# 1-Schematic_BluePill.net
KiCad netlist of a schematic drawn in EasyEDA
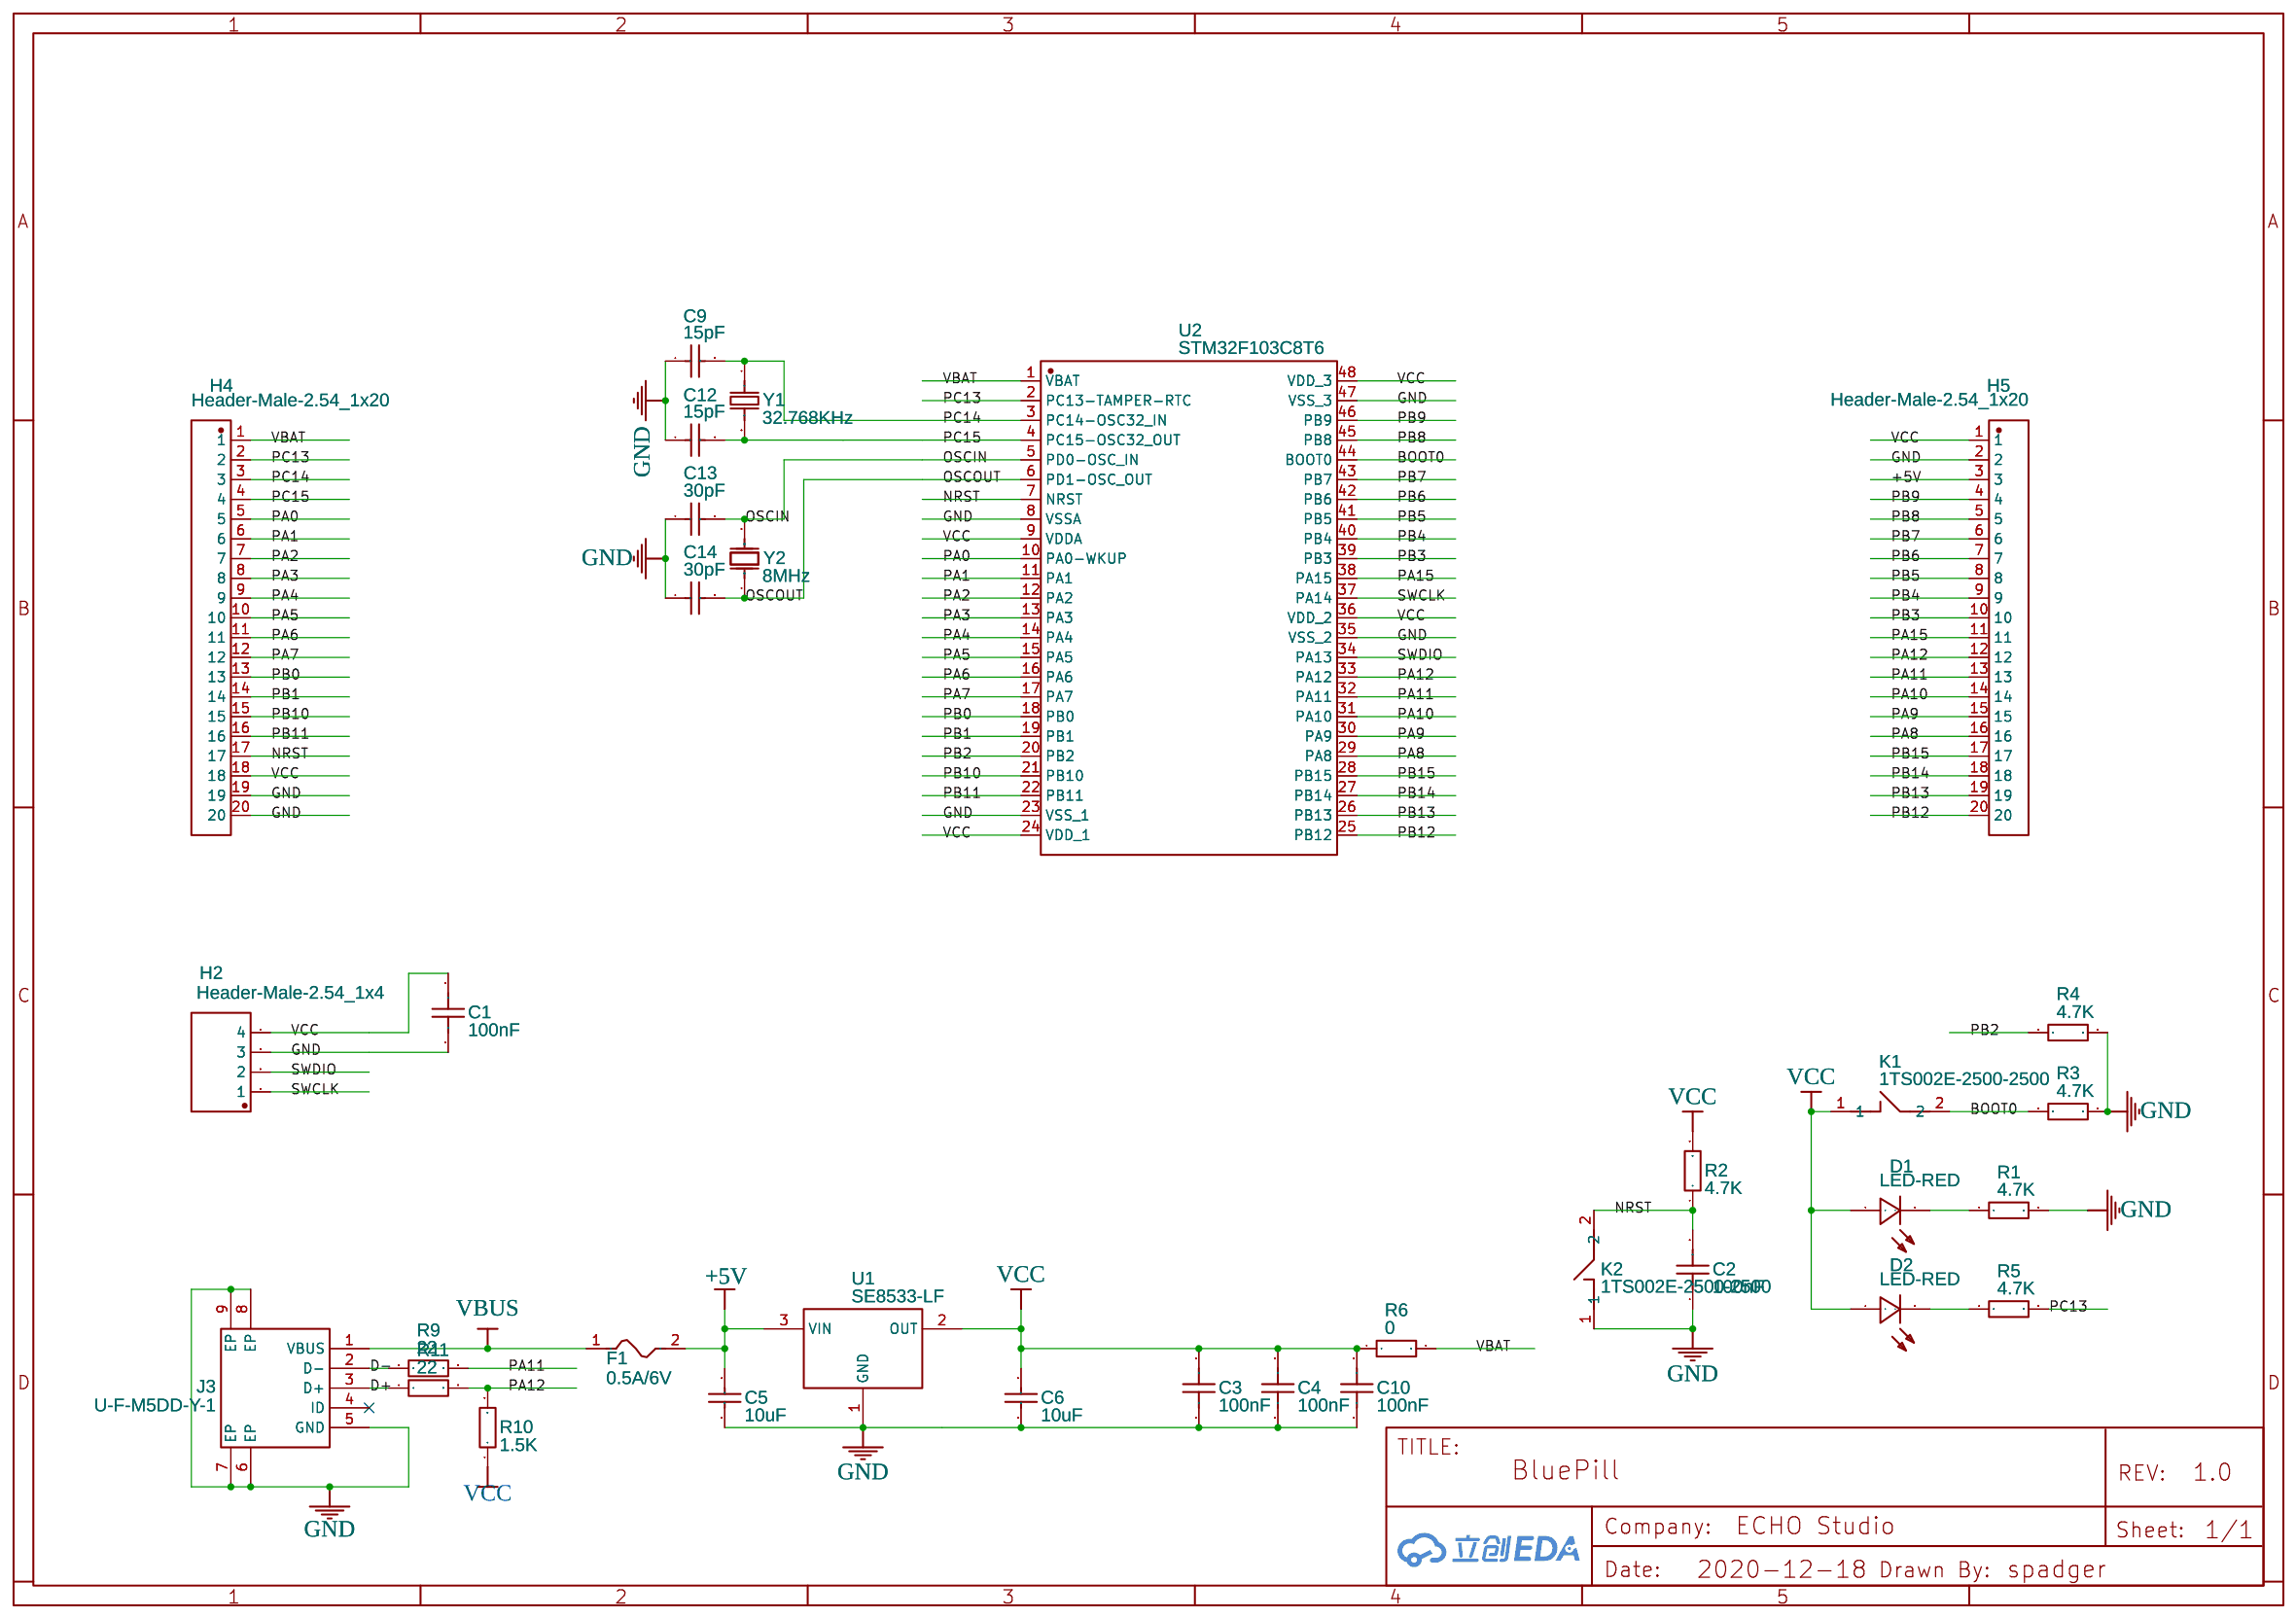
[diagram p0: schematic sheet]

(export (version "E")
  (design (tool "Eeschema 10.0.6"))
  (components
    (comp (ref "C1")
      (value "100nF")
      (fields
        (field (name "BOM_Manufacturer Part") "CC0603KRX7R9BB104")
        (field (name "BOM_Supplier Part") "C14663")
      )
      (libsource (lib "") (part "CC0603KRX7R9BB104"))
    )
    (comp (ref "C2")
      (value "100nF")
      (fields
        (field (name "BOM_Manufacturer Part") "CC0603KRX7R9BB104")
        (field (name "BOM_Supplier Part") "C14663")
      )
      (libsource (lib "") (part "CC0603KRX7R9BB104"))
    )
    (comp (ref "C3")
      (value "100nF")
      (fields
        (field (name "BOM_Manufacturer Part") "CC0603KRX7R9BB104")
        (field (name "BOM_Supplier Part") "C14663")
      )
      (libsource (lib "") (part "CC0603KRX7R9BB104"))
    )
    (comp (ref "C4")
      (value "100nF")
      (fields
        (field (name "BOM_Manufacturer Part") "CC0603KRX7R9BB104")
        (field (name "BOM_Supplier Part") "C14663")
      )
      (libsource (lib "") (part "CC0603KRX7R9BB104"))
    )
    (comp (ref "C5")
      (value "10uF")
      (fields
        (field (name "BOM_Manufacturer Part") "CL21A106KAYNNNE")
        (field (name "BOM_Supplier Part") "C15850")
      )
      (libsource (lib "") (part "CL21A106KAYNNNE"))
    )
    (comp (ref "C6")
      (value "10uF")
      (fields
        (field (name "BOM_Manufacturer Part") "CL21A106KAYNNNE")
        (field (name "BOM_Supplier Part") "C15850")
      )
      (libsource (lib "") (part "CL21A106KAYNNNE"))
    )
    (comp (ref "C9")
      (value "15pF")
      (fields
        (field (name "BOM_Manufacturer Part") "CL10C150JB8NNNC")
        (field (name "BOM_Supplier Part") "C1644")
      )
      (libsource (lib "") (part "CL10C150JB8NNNC"))
    )
    (comp (ref "C10")
      (value "100nF")
      (fields
        (field (name "BOM_Manufacturer Part") "CC0603KRX7R9BB104")
        (field (name "BOM_Supplier Part") "C14663")
      )
      (libsource (lib "") (part "CC0603KRX7R9BB104"))
    )
    (comp (ref "C12")
      (value "15pF")
      (fields
        (field (name "BOM_Manufacturer Part") "CL10C150JB8NNNC")
        (field (name "BOM_Supplier Part") "C1644")
      )
      (libsource (lib "") (part "CL10C150JB8NNNC"))
    )
    (comp (ref "C13")
      (value "30pF")
      (fields
        (field (name "BOM_Manufacturer Part") "CL10C300JB8NNNC")
        (field (name "BOM_Supplier Part") "C22397")
      )
      (libsource (lib "") (part "CL10C300JB8NNNC"))
    )
    (comp (ref "C14")
      (value "30pF")
      (fields
        (field (name "BOM_Manufacturer Part") "CL10C300JB8NNNC")
        (field (name "BOM_Supplier Part") "C22397")
      )
      (libsource (lib "") (part "CL10C300JB8NNNC"))
    )
    (comp (ref "D1")
      (value "LED-RED")
      (fields
        (field (name "BOM_Manufacturer Part") "FC-DA1608UGK-520D10")
        (field (name "BOM_Supplier Part") "C84267")
      )
      (libsource (lib "") (part "Unknown_950_-195"))
    )
    (comp (ref "D2")
      (value "LED-RED")
      (fields
        (field (name "BOM_Manufacturer Part") "FC-DA1608UGK-520D10")
        (field (name "BOM_Supplier Part") "C84267")
      )
      (libsource (lib "") (part "Unknown_950_-145"))
    )
    (comp (ref "F1")
      (value "0.5A/6V")
      (fields
        (field (name "BOM_Manufacturer Part") "SMD0805P050TF")
        (field (name "BOM_Supplier Part") "C130286")
      )
      (libsource (lib "") (part "Unknown_315_-135"))
    )
    (comp (ref "H2")
      (value "Header-Male-2.54_1x4")
      (fields
        (field (name "BOM_Manufacturer Part") "210S-1*4P L=11.6MMGold-plated black")
        (field (name "BOM_Supplier Part") "C124378")
      )
      (libsource (lib "") (part "Header-Male-2.54_1x4"))
    )
    (comp (ref "H4")
      (value "Header-Male-2.54_1x20")
      (fields
        (field (name "BOM_Manufacturer Part") "2.54mm 1*20PHeader")
        (field (name "BOM_Supplier Part") "C50981")
      )
      (libsource (lib "") (part "Header-Male-2.54_1x20"))
    )
    (comp (ref "H5")
      (value "Header-Male-2.54_1x20")
      (fields
        (field (name "BOM_Manufacturer Part") "2.54mm 1*20PHeader")
        (field (name "BOM_Supplier Part") "C50981")
      )
      (libsource (lib "") (part "Header-Male-2.54_1x20_1"))
    )
    (comp (ref "J3")
      (value "U-F-M5DD-Y-1")
      (fields (field (name "BOM_Supplier Part") "C91467"))
      (libsource (lib "") (part "U-F-M5DD-Y-1"))
    )
    (comp (ref "K1")
      (value "1TS002E-2500-2500")
      (fields (field (name "BOM_Supplier Part") "C329185"))
      (libsource (lib "") (part "1TS002E-2500-2500_1"))
    )
    (comp (ref "K2")
      (value "1TS002E-2500-2500")
      (fields (field (name "BOM_Supplier Part") "C329185"))
      (libsource (lib "") (part "1TS002E-2500-2500"))
    )
    (comp (ref "R1")
      (value "4.7K")
      (fields
        (field (name "BOM_Manufacturer Part") "0603WAF4701T5E")
        (field (name "BOM_Supplier Part") "C23162")
      )
      (libsource (lib "") (part "0603WAF4701T5E_1"))
    )
    (comp (ref "R2")
      (value "4.7K")
      (fields
        (field (name "BOM_Manufacturer Part") "0603WAF4701T5E")
        (field (name "BOM_Supplier Part") "C23162")
      )
      (libsource (lib "") (part "0603WAF4701T5E_2"))
    )
    (comp (ref "R3")
      (value "4.7K")
      (fields
        (field (name "BOM_Manufacturer Part") "0603WAF4701T5E")
        (field (name "BOM_Supplier Part") "C23162")
      )
      (libsource (lib "") (part "0603WAF4701T5E"))
    )
    (comp (ref "R4")
      (value "4.7K")
      (fields
        (field (name "BOM_Manufacturer Part") "0603WAF4701T5E")
        (field (name "BOM_Supplier Part") "C23162")
      )
      (libsource (lib "") (part "0603WAF4701T5E_1"))
    )
    (comp (ref "R5")
      (value "4.7K")
      (fields
        (field (name "BOM_Manufacturer Part") "0603WAF4701T5E")
        (field (name "BOM_Supplier Part") "C23162")
      )
      (libsource (lib "") (part "0603WAF4701T5E_1"))
    )
    (comp (ref "R6")
      (value "0")
      (fields
        (field (name "BOM_Manufacturer Part") "0603WAF0000T5E")
        (field (name "BOM_Supplier Part") "C21189")
      )
      (libsource (lib "") (part "0603WAF0000T5E"))
    )
    (comp (ref "R9")
      (value "22")
      (fields
        (field (name "BOM_Manufacturer Part") "0603WAF220JT5E")
        (field (name "BOM_Supplier Part") "C23345")
      )
      (libsource (lib "") (part "0603WAF220JT5E"))
    )
    (comp (ref "R10")
      (value "1.5K")
      (fields
        (field (name "BOM_Manufacturer Part") "0603WAF1501T5E")
        (field (name "BOM_Supplier Part") "C22843")
      )
      (libsource (lib "") (part "0603WAF1501T5E"))
    )
    (comp (ref "R11")
      (value "22")
      (fields
        (field (name "BOM_Manufacturer Part") "0603WAF220JT5E")
        (field (name "BOM_Supplier Part") "C23345")
      )
      (libsource (lib "") (part "0603WAF220JT5E"))
    )
    (comp (ref "U1")
      (value "SE8533-LF")
      (fields (field (name "BOM_Supplier Part") "C115016"))
      (libsource (lib "") (part "SE8533-LF"))
    )
    (comp (ref "U2")
      (value "STM32F103C8T6")
      (fields (field (name "BOM_Supplier Part") "C8734"))
      (libsource (lib "") (part "STM32F103C8T6"))
    )
    (comp (ref "Y1")
      (value "32.768KHz")
      (fields
        (field (name "BOM_Manufacturer Part") "DT-38 32.768KHz")
        (field (name "BOM_Supplier Part") "C93228")
      )
      (libsource (lib "") (part "DT-38 32.768KHz"))
    )
    (comp (ref "Y2")
      (value "8MHz")
      (fields (field (name "BOM_Supplier Part") "C107425"))
      (libsource (lib "") (part "HC-49S 8MHz 20pF 30PPM"))
    )
  )
  (nets
    (net (code "1") (name "+5V") (class "Default")
      (node (ref "C5") (pin "2") (pinfunction "2_2") (pintype "input"))
      (node (ref "F1") (pin "2") (pinfunction "2_2") (pintype "unspecified"))
      (node (ref "H5") (pin "3") (pinfunction "3_3") (pintype "unspecified"))
      (node (ref "U1") (pin "3") (pinfunction "VIN_3") (pintype "unspecified"))
    )
    (net (code "2") (name "/BOOT0") (class "Default")
      (node (ref "K1") (pin "2") (pinfunction "2_2") (pintype "unspecified"))
      (node (ref "R3") (pin "2") (pinfunction "2_2") (pintype "input"))
      (node (ref "U2") (pin "44") (pinfunction "BOOT0_44") (pintype "unspecified"))
    )
    (net (code "3") (name "/D+") (class "Default")
      (node (ref "J3") (pin "3") (pinfunction "D+_3") (pintype "unspecified"))
      (node (ref "R11") (pin "1") (pinfunction "1_1") (pintype "input"))
    )
    (net (code "4") (name "/D-") (class "Default")
      (node (ref "J3") (pin "2") (pinfunction "D-_2") (pintype "unspecified"))
      (node (ref "R9") (pin "1") (pinfunction "1_1") (pintype "input"))
    )
    (net (code "5") (name "/NRST") (class "Default")
      (node (ref "C2") (pin "2") (pinfunction "2_2") (pintype "unspecified"))
      (node (ref "H4") (pin "17") (pinfunction "17_17") (pintype "unspecified"))
      (node (ref "K2") (pin "2") (pinfunction "2_2") (pintype "unspecified"))
      (node (ref "R2") (pin "1") (pinfunction "1_1") (pintype "input"))
      (node (ref "U2") (pin "7") (pinfunction "NRST_7") (pintype "unspecified"))
    )
    (net (code "6") (name "/OSCIN") (class "Default")
      (node (ref "C13") (pin "2") (pinfunction "2_2") (pintype "input"))
      (node (ref "U2") (pin "5") (pinfunction "PD0-OSC_IN_5") (pintype "unspecified"))
      (node (ref "Y2") (pin "2") (pinfunction "OSC2_2") (pintype "input"))
    )
    (net (code "7") (name "/OSCOUT") (class "Default")
      (node (ref "C14") (pin "2") (pinfunction "2_2") (pintype "input"))
      (node (ref "U2") (pin "6") (pinfunction "PD1-OSC_OUT_6") (pintype "unspecified"))
      (node (ref "Y2") (pin "1") (pinfunction "OSC1_1") (pintype "input"))
    )
    (net (code "8") (name "/PA0") (class "Default")
      (node (ref "H4") (pin "5") (pinfunction "5_5") (pintype "unspecified"))
      (node (ref "U2") (pin "10") (pinfunction "PA0-WKUP_10") (pintype "unspecified"))
    )
    (net (code "9") (name "/PA1") (class "Default")
      (node (ref "H4") (pin "6") (pinfunction "6_6") (pintype "unspecified"))
      (node (ref "U2") (pin "11") (pinfunction "PA1_11") (pintype "unspecified"))
    )
    (net (code "10") (name "/PA2") (class "Default")
      (node (ref "H4") (pin "7") (pinfunction "7_7") (pintype "unspecified"))
      (node (ref "U2") (pin "12") (pinfunction "PA2_12") (pintype "unspecified"))
    )
    (net (code "11") (name "/PA3") (class "Default")
      (node (ref "H4") (pin "8") (pinfunction "8_8") (pintype "unspecified"))
      (node (ref "U2") (pin "13") (pinfunction "PA3_13") (pintype "unspecified"))
    )
    (net (code "12") (name "/PA4") (class "Default")
      (node (ref "H4") (pin "9") (pinfunction "9_9") (pintype "unspecified"))
      (node (ref "U2") (pin "14") (pinfunction "PA4_14") (pintype "unspecified"))
    )
    (net (code "13") (name "/PA5") (class "Default")
      (node (ref "H4") (pin "10") (pinfunction "10_10") (pintype "unspecified"))
      (node (ref "U2") (pin "15") (pinfunction "PA5_15") (pintype "unspecified"))
    )
    (net (code "14") (name "/PA6") (class "Default")
      (node (ref "H4") (pin "11") (pinfunction "11_11") (pintype "unspecified"))
      (node (ref "U2") (pin "16") (pinfunction "PA6_16") (pintype "unspecified"))
    )
    (net (code "15") (name "/PA7") (class "Default")
      (node (ref "H4") (pin "12") (pinfunction "12_12") (pintype "unspecified"))
      (node (ref "U2") (pin "17") (pinfunction "PA7_17") (pintype "unspecified"))
    )
    (net (code "16") (name "/PA8") (class "Default")
      (node (ref "H5") (pin "16") (pinfunction "16_16") (pintype "unspecified"))
      (node (ref "U2") (pin "29") (pinfunction "PA8_29") (pintype "unspecified"))
    )
    (net (code "17") (name "/PA9") (class "Default")
      (node (ref "H5") (pin "15") (pinfunction "15_15") (pintype "unspecified"))
      (node (ref "U2") (pin "30") (pinfunction "PA9_30") (pintype "unspecified"))
    )
    (net (code "18") (name "/PA10") (class "Default")
      (node (ref "H5") (pin "14") (pinfunction "14_14") (pintype "unspecified"))
      (node (ref "U2") (pin "31") (pinfunction "PA10_31") (pintype "unspecified"))
    )
    (net (code "19") (name "/PA11") (class "Default")
      (node (ref "H5") (pin "13") (pinfunction "13_13") (pintype "unspecified"))
      (node (ref "R9") (pin "2") (pinfunction "2_2") (pintype "input"))
      (node (ref "U2") (pin "32") (pinfunction "PA11_32") (pintype "unspecified"))
    )
    (net (code "20") (name "/PA12") (class "Default")
      (node (ref "H5") (pin "12") (pinfunction "12_12") (pintype "unspecified"))
      (node (ref "R10") (pin "2") (pinfunction "2_2") (pintype "input"))
      (node (ref "R11") (pin "2") (pinfunction "2_2") (pintype "input"))
      (node (ref "U2") (pin "33") (pinfunction "PA12_33") (pintype "unspecified"))
    )
    (net (code "21") (name "/PA15") (class "Default")
      (node (ref "H5") (pin "11") (pinfunction "11_11") (pintype "unspecified"))
      (node (ref "U2") (pin "38") (pinfunction "PA15_38") (pintype "unspecified"))
    )
    (net (code "22") (name "/PB0") (class "Default")
      (node (ref "H4") (pin "13") (pinfunction "13_13") (pintype "unspecified"))
      (node (ref "U2") (pin "18") (pinfunction "PB0_18") (pintype "unspecified"))
    )
    (net (code "23") (name "/PB1") (class "Default")
      (node (ref "H4") (pin "14") (pinfunction "14_14") (pintype "unspecified"))
      (node (ref "U2") (pin "19") (pinfunction "PB1_19") (pintype "unspecified"))
    )
    (net (code "24") (name "/PB2") (class "Default")
      (node (ref "R4") (pin "1") (pinfunction "1_1") (pintype "input"))
      (node (ref "U2") (pin "20") (pinfunction "PB2_20") (pintype "unspecified"))
    )
    (net (code "25") (name "/PB3") (class "Default")
      (node (ref "H5") (pin "10") (pinfunction "10_10") (pintype "unspecified"))
      (node (ref "U2") (pin "39") (pinfunction "PB3_39") (pintype "unspecified"))
    )
    (net (code "26") (name "/PB4") (class "Default")
      (node (ref "H5") (pin "9") (pinfunction "9_9") (pintype "unspecified"))
      (node (ref "U2") (pin "40") (pinfunction "PB4_40") (pintype "unspecified"))
    )
    (net (code "27") (name "/PB5") (class "Default")
      (node (ref "H5") (pin "8") (pinfunction "8_8") (pintype "unspecified"))
      (node (ref "U2") (pin "41") (pinfunction "PB5_41") (pintype "unspecified"))
    )
    (net (code "28") (name "/PB6") (class "Default")
      (node (ref "H5") (pin "7") (pinfunction "7_7") (pintype "unspecified"))
      (node (ref "U2") (pin "42") (pinfunction "PB6_42") (pintype "unspecified"))
    )
    (net (code "29") (name "/PB7") (class "Default")
      (node (ref "H5") (pin "6") (pinfunction "6_6") (pintype "unspecified"))
      (node (ref "U2") (pin "43") (pinfunction "PB7_43") (pintype "unspecified"))
    )
    (net (code "30") (name "/PB8") (class "Default")
      (node (ref "H5") (pin "5") (pinfunction "5_5") (pintype "unspecified"))
      (node (ref "U2") (pin "45") (pinfunction "PB8_45") (pintype "unspecified"))
    )
    (net (code "31") (name "/PB9") (class "Default")
      (node (ref "H5") (pin "4") (pinfunction "4_4") (pintype "unspecified"))
      (node (ref "U2") (pin "46") (pinfunction "PB9_46") (pintype "unspecified"))
    )
    (net (code "32") (name "/PB10") (class "Default")
      (node (ref "H4") (pin "15") (pinfunction "15_15") (pintype "unspecified"))
      (node (ref "U2") (pin "21") (pinfunction "PB10_21") (pintype "unspecified"))
    )
    (net (code "33") (name "/PB11") (class "Default")
      (node (ref "H4") (pin "16") (pinfunction "16_16") (pintype "unspecified"))
      (node (ref "U2") (pin "22") (pinfunction "PB11_22") (pintype "unspecified"))
    )
    (net (code "34") (name "/PB12") (class "Default")
      (node (ref "H5") (pin "20") (pinfunction "20_20") (pintype "unspecified"))
      (node (ref "U2") (pin "25") (pinfunction "PB12_25") (pintype "unspecified"))
    )
    (net (code "35") (name "/PB13") (class "Default")
      (node (ref "H5") (pin "19") (pinfunction "19_19") (pintype "unspecified"))
      (node (ref "U2") (pin "26") (pinfunction "PB13_26") (pintype "unspecified"))
    )
    (net (code "36") (name "/PB14") (class "Default")
      (node (ref "H5") (pin "18") (pinfunction "18_18") (pintype "unspecified"))
      (node (ref "U2") (pin "27") (pinfunction "PB14_27") (pintype "unspecified"))
    )
    (net (code "37") (name "/PB15") (class "Default")
      (node (ref "H5") (pin "17") (pinfunction "17_17") (pintype "unspecified"))
      (node (ref "U2") (pin "28") (pinfunction "PB15_28") (pintype "unspecified"))
    )
    (net (code "38") (name "/PC13") (class "Default")
      (node (ref "H4") (pin "2") (pinfunction "2_2") (pintype "unspecified"))
      (node (ref "R5") (pin "2") (pinfunction "2_2") (pintype "input"))
      (node (ref "U2") (pin "2") (pinfunction "PC13-TAMPER-RTC_2") (pintype "unspecified"))
    )
    (net (code "39") (name "/PC14") (class "Default")
      (node (ref "C9") (pin "2") (pinfunction "2_2") (pintype "input"))
      (node (ref "H4") (pin "3") (pinfunction "3_3") (pintype "unspecified"))
      (node (ref "U2") (pin "3") (pinfunction "PC14-OSC32_IN_3") (pintype "unspecified"))
      (node (ref "Y1") (pin "1") (pinfunction "1_1") (pintype "unspecified"))
    )
    (net (code "40") (name "/PC15") (class "Default")
      (node (ref "C12") (pin "2") (pinfunction "2_2") (pintype "input"))
      (node (ref "H4") (pin "4") (pinfunction "4_4") (pintype "unspecified"))
      (node (ref "U2") (pin "4") (pinfunction "PC15-OSC32_OUT_4") (pintype "unspecified"))
      (node (ref "Y1") (pin "2") (pinfunction "2_2") (pintype "unspecified"))
    )
    (net (code "41") (name "/SWCLK") (class "Default")
      (node (ref "H2") (pin "1") (pinfunction "1_1") (pintype "unspecified"))
      (node (ref "U2") (pin "37") (pinfunction "PA14_37") (pintype "unspecified"))
    )
    (net (code "42") (name "/SWDIO") (class "Default")
      (node (ref "H2") (pin "2") (pinfunction "2_2") (pintype "unspecified"))
      (node (ref "U2") (pin "34") (pinfunction "PA13_34") (pintype "unspecified"))
    )
    (net (code "43") (name "/VBAT") (class "Default")
      (node (ref "H4") (pin "1") (pinfunction "1_1") (pintype "unspecified"))
      (node (ref "R6") (pin "2") (pinfunction "2_2") (pintype "input"))
      (node (ref "U2") (pin "1") (pinfunction "VBAT_1") (pintype "unspecified"))
    )
    (net (code "44") (name "GND") (class "Default")
      (node (ref "C1") (pin "1") (pinfunction "1_1") (pintype "unspecified"))
      (node (ref "C10") (pin "1") (pinfunction "1_1") (pintype "unspecified"))
      (node (ref "C12") (pin "1") (pinfunction "1_1") (pintype "input"))
      (node (ref "C13") (pin "1") (pinfunction "1_1") (pintype "input"))
      (node (ref "C14") (pin "1") (pinfunction "1_1") (pintype "input"))
      (node (ref "C2") (pin "1") (pinfunction "1_1") (pintype "unspecified"))
      (node (ref "C3") (pin "1") (pinfunction "1_1") (pintype "unspecified"))
      (node (ref "C4") (pin "1") (pinfunction "1_1") (pintype "unspecified"))
      (node (ref "C5") (pin "1") (pinfunction "1_1") (pintype "input"))
      (node (ref "C6") (pin "1") (pinfunction "1_1") (pintype "input"))
      (node (ref "C9") (pin "1") (pinfunction "1_1") (pintype "input"))
      (node (ref "H2") (pin "3") (pinfunction "3_3") (pintype "unspecified"))
      (node (ref "H4") (pin "19") (pinfunction "19_19") (pintype "unspecified"))
      (node (ref "H4") (pin "20") (pinfunction "20_20") (pintype "unspecified"))
      (node (ref "H5") (pin "2") (pinfunction "2_2") (pintype "unspecified"))
      (node (ref "J3") (pin "5") (pinfunction "GND_5") (pintype "unspecified"))
      (node (ref "J3") (pin "6") (pinfunction "EP_6") (pintype "unspecified"))
      (node (ref "J3") (pin "7") (pinfunction "EP_7") (pintype "unspecified"))
      (node (ref "J3") (pin "8") (pinfunction "EP_8") (pintype "unspecified"))
      (node (ref "J3") (pin "9") (pinfunction "EP_9") (pintype "unspecified"))
      (node (ref "K2") (pin "1") (pinfunction "1_1") (pintype "unspecified"))
      (node (ref "R1") (pin "2") (pinfunction "2_2") (pintype "input"))
      (node (ref "R3") (pin "1") (pinfunction "1_1") (pintype "input"))
      (node (ref "R4") (pin "2") (pinfunction "2_2") (pintype "input"))
      (node (ref "U1") (pin "1") (pinfunction "GND_1") (pintype "unspecified"))
      (node (ref "U2") (pin "23") (pinfunction "VSS_1_23") (pintype "unspecified"))
      (node (ref "U2") (pin "35") (pinfunction "VSS_2_35") (pintype "unspecified"))
      (node (ref "U2") (pin "47") (pinfunction "VSS_3_47") (pintype "unspecified"))
      (node (ref "U2") (pin "8") (pinfunction "VSSA_8") (pintype "unspecified"))
    )
    (net (code "45") (name "Net-(D1--)") (class "Default")
      (node (ref "D1") (pin "2") (pinfunction "-_2") (pintype "unspecified"))
      (node (ref "R1") (pin "1") (pinfunction "1_1") (pintype "input"))
    )
    (net (code "46") (name "Net-(D2--)") (class "Default")
      (node (ref "D2") (pin "2") (pinfunction "-_2") (pintype "unspecified"))
      (node (ref "R5") (pin "1") (pinfunction "1_1") (pintype "input"))
    )
    (net (code "47") (name "VBUS") (class "Default")
      (node (ref "F1") (pin "1") (pinfunction "1_1") (pintype "unspecified"))
      (node (ref "J3") (pin "1") (pinfunction "VBUS_1") (pintype "unspecified"))
    )
    (net (code "48") (name "VCC") (class "Default")
      (node (ref "C1") (pin "2") (pinfunction "2_2") (pintype "unspecified"))
      (node (ref "C10") (pin "2") (pinfunction "2_2") (pintype "unspecified"))
      (node (ref "C3") (pin "2") (pinfunction "2_2") (pintype "unspecified"))
      (node (ref "C4") (pin "2") (pinfunction "2_2") (pintype "unspecified"))
      (node (ref "C6") (pin "2") (pinfunction "2_2") (pintype "input"))
      (node (ref "D1") (pin "1") (pinfunction "+_1") (pintype "unspecified"))
      (node (ref "D2") (pin "1") (pinfunction "+_1") (pintype "unspecified"))
      (node (ref "H2") (pin "4") (pinfunction "4_4") (pintype "unspecified"))
      (node (ref "H4") (pin "18") (pinfunction "18_18") (pintype "unspecified"))
      (node (ref "H5") (pin "1") (pinfunction "1_1") (pintype "unspecified"))
      (node (ref "K1") (pin "1") (pinfunction "1_1") (pintype "unspecified"))
      (node (ref "R10") (pin "1") (pinfunction "1_1") (pintype "input"))
      (node (ref "R2") (pin "2") (pinfunction "2_2") (pintype "input"))
      (node (ref "R6") (pin "1") (pinfunction "1_1") (pintype "input"))
      (node (ref "U1") (pin "2") (pinfunction "OUT_2") (pintype "unspecified"))
      (node (ref "U2") (pin "24") (pinfunction "VDD_1_24") (pintype "unspecified"))
      (node (ref "U2") (pin "36") (pinfunction "VDD_2_36") (pintype "unspecified"))
      (node (ref "U2") (pin "48") (pinfunction "VDD_3_48") (pintype "unspecified"))
      (node (ref "U2") (pin "9") (pinfunction "VDDA_9") (pintype "unspecified"))
    )
    (net (code "49") (name "unconnected-(J3-ID-Pad4)") (class "Default")
      (node (ref "J3") (pin "4") (pinfunction "ID_4") (pintype "unspecified+no_connect"))
    )
  )
)
